# rtlsdr_lna.net
KiCad netlist of a schematic drawn in EAGLE
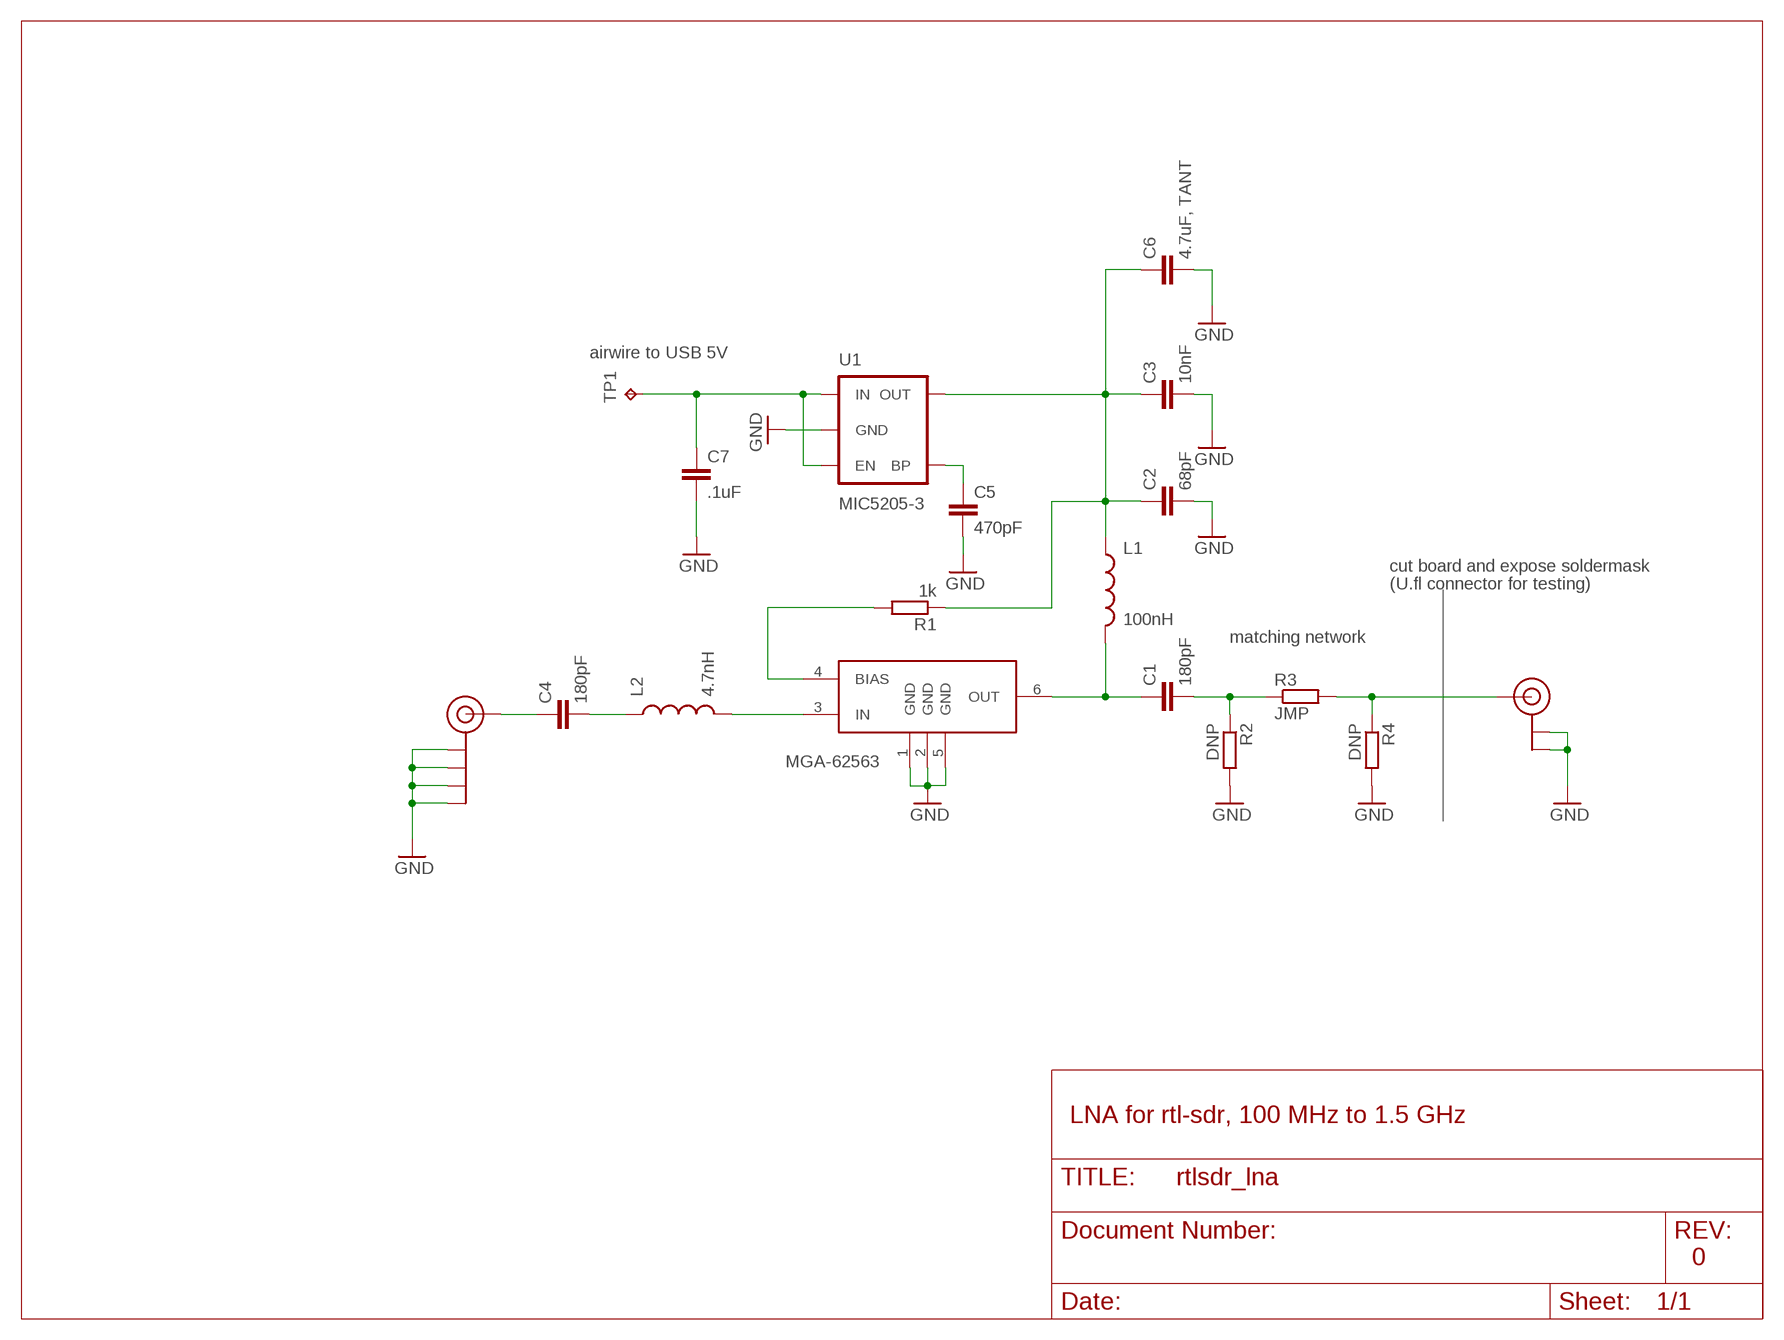
[diagram p0: schematic, sheet 1]

(export (version "E")
  (design (tool "Eeschema 10.0.6"))
  (components
    (comp (ref "C1")
      (value "180pF")
      (footprint "eagle-import:C0402")
      (libsource (lib "eagle-import") (part "C-EUC0402"))
    )
    (comp (ref "C2")
      (value "68pF")
      (footprint "eagle-import:C0402")
      (libsource (lib "eagle-import") (part "C-EUC0402"))
    )
    (comp (ref "C3")
      (value "10nF")
      (footprint "eagle-import:C0402")
      (libsource (lib "eagle-import") (part "C-EUC0402"))
    )
    (comp (ref "C4")
      (value "180pF")
      (footprint "eagle-import:C0402")
      (libsource (lib "eagle-import") (part "C-EUC0402"))
    )
    (comp (ref "C5")
      (value "470pF")
      (footprint "eagle-import:C0402")
      (libsource (lib "eagle-import") (part "C-EUC0402"))
    )
    (comp (ref "C6")
      (value "4.7uF, TANT")
      (footprint "eagle-import:C0805")
      (libsource (lib "eagle-import") (part "C-EUC0805"))
    )
    (comp (ref "C7")
      (value ".1uF")
      (footprint "eagle-import:C0603")
      (libsource (lib "eagle-import") (part "C-EUC0603"))
    )
    (comp (ref "J$1")
      (value "SMA_EDGE")
      (footprint "eagle-import:SMA-EDGE")
      (libsource (lib "eagle-import") (part "SMA_EDGE"))
    )
    (comp (ref "L1")
      (value "100nH")
      (footprint "eagle-import:0603")
      (libsource (lib "eagle-import") (part "INDUCTOR0603"))
    )
    (comp (ref "L2")
      (value "4.7nH")
      (footprint "eagle-import:C0402")
      (libsource (lib "eagle-import") (part "INDUCTOR0402"))
    )
    (comp (ref "R1")
      (value "1k")
      (footprint "eagle-import:R0402")
      (libsource (lib "eagle-import") (part "R-EU_R0402"))
    )
    (comp (ref "R2")
      (value "DNP")
      (footprint "eagle-import:R0402")
      (libsource (lib "eagle-import") (part "R-EU_R0402"))
    )
    (comp (ref "R3")
      (value "JMP")
      (footprint "eagle-import:R0402")
      (libsource (lib "eagle-import") (part "R-EU_R0402"))
    )
    (comp (ref "R4")
      (value "DNP")
      (footprint "eagle-import:R0402")
      (libsource (lib "eagle-import") (part "R-EU_R0402"))
    )
    (comp (ref "TP1")
      (value "TPTP20SQ")
      (footprint "eagle-import:TP20SQ")
      (libsource (lib "eagle-import") (part "TPTP20SQ"))
    )
    (comp (ref "U$1")
      (value "MGA-68563")
      (footprint "eagle-import:SOT363")
      (libsource (lib "eagle-import") (part "MGA-68563"))
    )
    (comp (ref "U$2")
      (value "U.FL")
      (footprint "eagle-import:U.FL")
      (libsource (lib "eagle-import") (part "U.FL"))
    )
    (comp (ref "U1")
      (value "MIC5205-3")
      (footprint "eagle-import:SOT23-5")
      (libsource (lib "eagle-import") (part "V_REG_LDOSMD"))
    )
  )
  (nets
    (net (code "1") (name "GND") (class "Default")
      (node (ref "C2") (pin "2") (pinfunction "2_2") (pintype "passive"))
      (node (ref "C3") (pin "2") (pinfunction "2_2") (pintype "passive"))
      (node (ref "C5") (pin "2") (pinfunction "2_2") (pintype "passive"))
      (node (ref "C6") (pin "2") (pinfunction "2_2") (pintype "passive"))
      (node (ref "C7") (pin "2") (pinfunction "2_2") (pintype "passive"))
      (node (ref "J$1") (pin "GND@0") (pinfunction "GND_GND@0") (pintype "bidirectional"))
      (node (ref "J$1") (pin "GND@1") (pinfunction "GND_GND@1") (pintype "bidirectional"))
      (node (ref "J$1") (pin "GND@2") (pinfunction "GND_GND@2") (pintype "bidirectional"))
      (node (ref "J$1") (pin "GND@3") (pinfunction "GND_GND@3") (pintype "bidirectional"))
      (node (ref "R2") (pin "2") (pinfunction "2_2") (pintype "passive"))
      (node (ref "R4") (pin "2") (pinfunction "2_2") (pintype "passive"))
      (node (ref "U$1") (pin "1") (pinfunction "GND_1") (pintype "power_in"))
      (node (ref "U$1") (pin "2") (pinfunction "GND_2") (pintype "power_in"))
      (node (ref "U$1") (pin "5") (pinfunction "GND_5") (pintype "power_in"))
      (node (ref "U$2") (pin "P$1") (pinfunction "GND_P$1") (pintype "bidirectional"))
      (node (ref "U$2") (pin "P$2") (pinfunction "GND_P$2") (pintype "bidirectional"))
      (node (ref "U1") (pin "2") (pinfunction "GND_2") (pintype "input"))
    )
    (net (code "2") (name "Net-(C1-Pad2)") (class "Default")
      (node (ref "C1") (pin "2") (pinfunction "2_2") (pintype "passive"))
      (node (ref "R2") (pin "1") (pinfunction "1_1") (pintype "passive"))
      (node (ref "R3") (pin "1") (pinfunction "1_1") (pintype "passive"))
    )
    (net (code "3") (name "Net-(C4-Pad2)") (class "Default")
      (node (ref "C4") (pin "2") (pinfunction "2_2") (pintype "passive"))
      (node (ref "L2") (pin "1") (pinfunction "1_1") (pintype "passive"))
    )
    (net (code "4") (name "Net-(J$1-SIGNAL)") (class "Default")
      (node (ref "C4") (pin "1") (pinfunction "1_1") (pintype "passive"))
      (node (ref "J$1") (pin "SIG") (pinfunction "SIGNAL_SIG") (pintype "bidirectional"))
    )
    (net (code "5") (name "Net-(U$1-BIAS)") (class "Default")
      (node (ref "R1") (pin "2") (pinfunction "2_2") (pintype "passive"))
      (node (ref "U$1") (pin "4") (pinfunction "BIAS_4") (pintype "input"))
    )
    (net (code "6") (name "Net-(U$1-IN)") (class "Default")
      (node (ref "L2") (pin "2") (pinfunction "2_2") (pintype "passive"))
      (node (ref "U$1") (pin "3") (pinfunction "IN_3") (pintype "bidirectional"))
    )
    (net (code "7") (name "Net-(U$1-OUT)") (class "Default")
      (node (ref "C1") (pin "1") (pinfunction "1_1") (pintype "passive"))
      (node (ref "L1") (pin "2") (pinfunction "2_2") (pintype "passive"))
      (node (ref "U$1") (pin "6") (pinfunction "OUT_6") (pintype "bidirectional"))
    )
    (net (code "8") (name "Net-(U$2-SIGNAL)") (class "Default")
      (node (ref "R3") (pin "2") (pinfunction "2_2") (pintype "passive"))
      (node (ref "R4") (pin "1") (pinfunction "1_1") (pintype "passive"))
      (node (ref "U$2") (pin "P$3") (pinfunction "SIGNAL_P$3") (pintype "bidirectional"))
    )
    (net (code "9") (name "Net-(U1-BP)") (class "Default")
      (node (ref "C5") (pin "1") (pinfunction "1_1") (pintype "passive"))
      (node (ref "U1") (pin "4") (pinfunction "BP_4") (pintype "input"))
    )
    (net (code "10") (name "Net-(U1-EN)") (class "Default")
      (node (ref "C7") (pin "1") (pinfunction "1_1") (pintype "passive"))
      (node (ref "TP1") (pin "TP") (pinfunction "TP_TP") (pintype "input"))
      (node (ref "U1") (pin "1") (pinfunction "IN_1") (pintype "input"))
      (node (ref "U1") (pin "3") (pinfunction "EN_3") (pintype "input"))
    )
    (net (code "11") (name "Net-(U1-OUT)") (class "Default")
      (node (ref "C2") (pin "1") (pinfunction "1_1") (pintype "passive"))
      (node (ref "C3") (pin "1") (pinfunction "1_1") (pintype "passive"))
      (node (ref "C6") (pin "1") (pinfunction "1_1") (pintype "passive"))
      (node (ref "L1") (pin "1") (pinfunction "1_1") (pintype "passive"))
      (node (ref "R1") (pin "1") (pinfunction "1_1") (pintype "passive"))
      (node (ref "U1") (pin "5") (pinfunction "OUT_5") (pintype "passive"))
    )
  )
)
